# LTC2495Shield.net
KiCad netlist of a schematic drawn in EAGLE
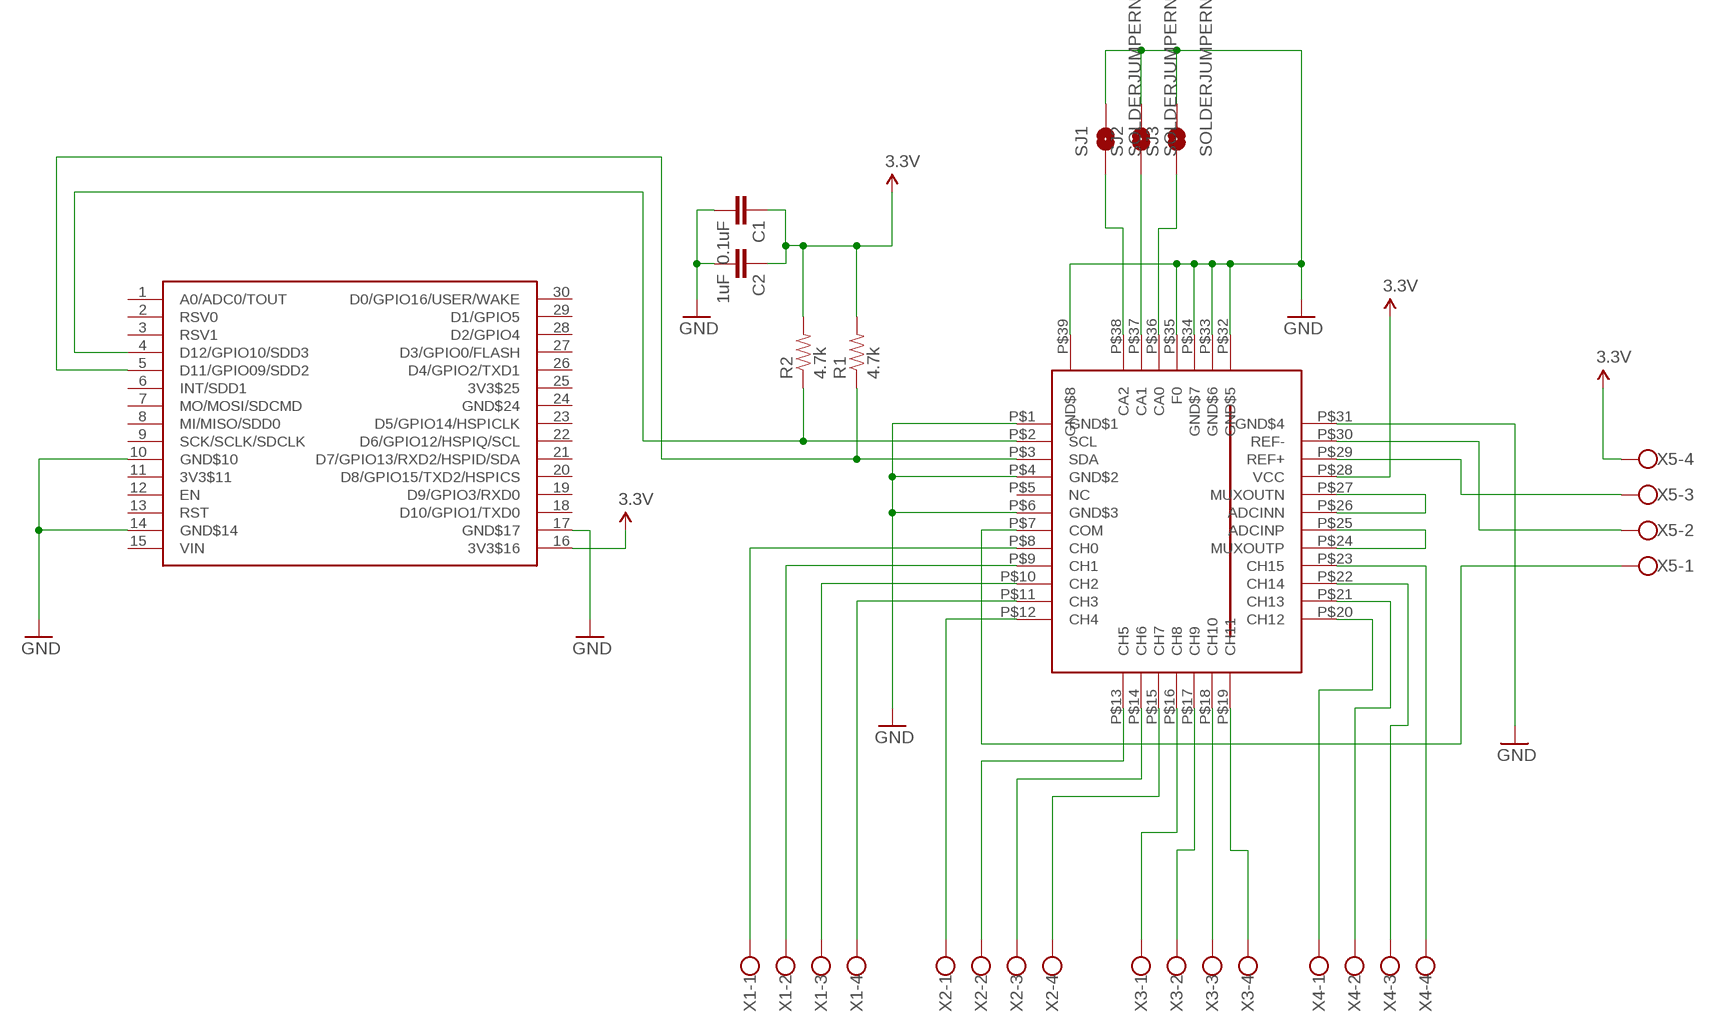
[diagram p0: schematic, sheet 1]

(export (version "E")
  (design (tool "Eeschema 10.0.6"))
  (components
    (comp (ref "C1")
      (value "0.1uF")
      (footprint "eagle-import:0402-CAP")
      (libsource (lib "eagle-import") (part "CAP0402-CAP"))
    )
    (comp (ref "C2")
      (value "1uF")
      (footprint "eagle-import:0402-CAP")
      (libsource (lib "eagle-import") (part "CAP0402-CAP"))
    )
    (comp (ref "R1")
      (value "4.7k")
      (footprint "eagle-import:0402-RES")
      (libsource (lib "eagle-import") (part "RESISTOR0402-RES"))
    )
    (comp (ref "R2")
      (value "4.7k")
      (footprint "eagle-import:0402-RES")
      (libsource (lib "eagle-import") (part "RESISTOR0402-RES"))
    )
    (comp (ref "SJ1")
      (value "SOLDERJUMPERNO")
      (footprint "eagle-import:SJ_2S-NO")
      (libsource (lib "eagle-import") (part "SOLDERJUMPERNO"))
    )
    (comp (ref "SJ2")
      (value "SOLDERJUMPERNO")
      (footprint "eagle-import:SJ_2S-NO")
      (libsource (lib "eagle-import") (part "SOLDERJUMPERNO"))
    )
    (comp (ref "SJ3")
      (value "SOLDERJUMPERNO")
      (footprint "eagle-import:SJ_2S-NO")
      (libsource (lib "eagle-import") (part "SOLDERJUMPERNO"))
    )
    (comp (ref "U$1")
      (value "NERDSHIELD")
      (footprint "eagle-import:NERDUINO_STACK")
      (libsource (lib "eagle-import") (part "NERDSHIELD"))
    )
    (comp (ref "U$3")
      (value "LTC2495")
      (footprint "eagle-import:UHF38")
      (libsource (lib "eagle-import") (part "LTC2495"))
    )
    (comp (ref "X1")
      (value "W237-4")
      (footprint "eagle-import:W237-4")
      (libsource (lib "eagle-import") (part "W237-4"))
    )
    (comp (ref "X2")
      (value "W237-4")
      (footprint "eagle-import:W237-4")
      (libsource (lib "eagle-import") (part "W237-4"))
    )
    (comp (ref "X3")
      (value "W237-4")
      (footprint "eagle-import:W237-4")
      (libsource (lib "eagle-import") (part "W237-4"))
    )
    (comp (ref "X4")
      (value "W237-4")
      (footprint "eagle-import:W237-4")
      (libsource (lib "eagle-import") (part "W237-4"))
    )
    (comp (ref "X5")
      (value "W237-4")
      (footprint "eagle-import:W237-4")
      (libsource (lib "eagle-import") (part "W237-4"))
    )
  )
  (nets
    (net (code "1") (name "3.3V") (class "Default")
      (node (ref "C1") (pin "1") (pinfunction "1_1") (pintype "passive"))
      (node (ref "C2") (pin "1") (pinfunction "1_1") (pintype "passive"))
      (node (ref "R1") (pin "2") (pinfunction "2_2") (pintype "passive"))
      (node (ref "R2") (pin "2") (pinfunction "2_2") (pintype "passive"))
      (node (ref "U$1") (pin "16") (pinfunction "3V3$16_16") (pintype "bidirectional"))
      (node (ref "U$3") (pin "P$28") (pinfunction "VCC_P$28") (pintype "bidirectional"))
      (node (ref "X5") (pin "4") (pinfunction "KL_4") (pintype "passive"))
    )
    (net (code "2") (name "GND") (class "Default")
      (node (ref "C1") (pin "2") (pinfunction "2_2") (pintype "passive"))
      (node (ref "C2") (pin "2") (pinfunction "2_2") (pintype "passive"))
      (node (ref "SJ1") (pin "2") (pinfunction "2_2") (pintype "passive"))
      (node (ref "SJ2") (pin "2") (pinfunction "2_2") (pintype "passive"))
      (node (ref "SJ3") (pin "2") (pinfunction "2_2") (pintype "passive"))
      (node (ref "U$1") (pin "10") (pinfunction "GND$10_10") (pintype "bidirectional"))
      (node (ref "U$1") (pin "14") (pinfunction "GND$14_14") (pintype "bidirectional"))
      (node (ref "U$1") (pin "17") (pinfunction "GND$17_17") (pintype "bidirectional"))
      (node (ref "U$3") (pin "P$1") (pinfunction "GND$1_P$1") (pintype "bidirectional"))
      (node (ref "U$3") (pin "P$31") (pinfunction "GND$4_P$31") (pintype "bidirectional"))
      (node (ref "U$3") (pin "P$32") (pinfunction "GND$5_P$32") (pintype "bidirectional"))
      (node (ref "U$3") (pin "P$33") (pinfunction "GND$6_P$33") (pintype "bidirectional"))
      (node (ref "U$3") (pin "P$34") (pinfunction "GND$7_P$34") (pintype "bidirectional"))
      (node (ref "U$3") (pin "P$35") (pinfunction "F0_P$35") (pintype "bidirectional"))
      (node (ref "U$3") (pin "P$39") (pinfunction "GND$8_P$39") (pintype "bidirectional"))
      (node (ref "U$3") (pin "P$4") (pinfunction "GND$2_P$4") (pintype "bidirectional"))
      (node (ref "U$3") (pin "P$6") (pinfunction "GND$3_P$6") (pintype "bidirectional"))
    )
    (net (code "3") (name "Net-(U$1-D11{slash}GPIO09{slash}SDD2)") (class "Default")
      (node (ref "R1") (pin "1") (pinfunction "1_1") (pintype "passive"))
      (node (ref "U$1") (pin "5") (pinfunction "D11/GPIO09/SDD2_5") (pintype "bidirectional"))
      (node (ref "U$3") (pin "P$3") (pinfunction "SDA_P$3") (pintype "bidirectional"))
    )
    (net (code "4") (name "Net-(U$1-D12{slash}GPIO10{slash}SDD3)") (class "Default")
      (node (ref "R2") (pin "1") (pinfunction "1_1") (pintype "passive"))
      (node (ref "U$1") (pin "4") (pinfunction "D12/GPIO10/SDD3_4") (pintype "bidirectional"))
      (node (ref "U$3") (pin "P$2") (pinfunction "SCL_P$2") (pintype "bidirectional"))
    )
    (net (code "5") (name "Net-(U$3-ADCINN)") (class "Default")
      (node (ref "U$3") (pin "P$26") (pinfunction "ADCINN_P$26") (pintype "bidirectional"))
      (node (ref "U$3") (pin "P$27") (pinfunction "MUXOUTN_P$27") (pintype "bidirectional"))
    )
    (net (code "6") (name "Net-(U$3-ADCINP)") (class "Default")
      (node (ref "U$3") (pin "P$24") (pinfunction "MUXOUTP_P$24") (pintype "bidirectional"))
      (node (ref "U$3") (pin "P$25") (pinfunction "ADCINP_P$25") (pintype "bidirectional"))
    )
    (net (code "7") (name "Net-(U$3-CA0)") (class "Default")
      (node (ref "SJ3") (pin "1") (pinfunction "1_1") (pintype "passive"))
      (node (ref "U$3") (pin "P$36") (pinfunction "CA0_P$36") (pintype "bidirectional"))
    )
    (net (code "8") (name "Net-(U$3-CA1)") (class "Default")
      (node (ref "SJ2") (pin "1") (pinfunction "1_1") (pintype "passive"))
      (node (ref "U$3") (pin "P$37") (pinfunction "CA1_P$37") (pintype "bidirectional"))
    )
    (net (code "9") (name "Net-(U$3-CA2)") (class "Default")
      (node (ref "SJ1") (pin "1") (pinfunction "1_1") (pintype "passive"))
      (node (ref "U$3") (pin "P$38") (pinfunction "CA2_P$38") (pintype "bidirectional"))
    )
    (net (code "10") (name "Net-(U$3-CH0)") (class "Default")
      (node (ref "U$3") (pin "P$8") (pinfunction "CH0_P$8") (pintype "bidirectional"))
      (node (ref "X1") (pin "1") (pinfunction "KL_1") (pintype "passive"))
    )
    (net (code "11") (name "Net-(U$3-CH1)") (class "Default")
      (node (ref "U$3") (pin "P$9") (pinfunction "CH1_P$9") (pintype "bidirectional"))
      (node (ref "X1") (pin "2") (pinfunction "KL_2") (pintype "passive"))
    )
    (net (code "12") (name "Net-(U$3-CH2)") (class "Default")
      (node (ref "U$3") (pin "P$10") (pinfunction "CH2_P$10") (pintype "bidirectional"))
      (node (ref "X1") (pin "3") (pinfunction "KL_3") (pintype "passive"))
    )
    (net (code "13") (name "Net-(U$3-CH3)") (class "Default")
      (node (ref "U$3") (pin "P$11") (pinfunction "CH3_P$11") (pintype "bidirectional"))
      (node (ref "X1") (pin "4") (pinfunction "KL_4") (pintype "passive"))
    )
    (net (code "14") (name "Net-(U$3-CH4)") (class "Default")
      (node (ref "U$3") (pin "P$12") (pinfunction "CH4_P$12") (pintype "bidirectional"))
      (node (ref "X2") (pin "1") (pinfunction "KL_1") (pintype "passive"))
    )
    (net (code "15") (name "Net-(U$3-CH5)") (class "Default")
      (node (ref "U$3") (pin "P$13") (pinfunction "CH5_P$13") (pintype "bidirectional"))
      (node (ref "X2") (pin "2") (pinfunction "KL_2") (pintype "passive"))
    )
    (net (code "16") (name "Net-(U$3-CH6)") (class "Default")
      (node (ref "U$3") (pin "P$14") (pinfunction "CH6_P$14") (pintype "bidirectional"))
      (node (ref "X2") (pin "3") (pinfunction "KL_3") (pintype "passive"))
    )
    (net (code "17") (name "Net-(U$3-CH7)") (class "Default")
      (node (ref "U$3") (pin "P$15") (pinfunction "CH7_P$15") (pintype "bidirectional"))
      (node (ref "X2") (pin "4") (pinfunction "KL_4") (pintype "passive"))
    )
    (net (code "18") (name "Net-(U$3-CH8)") (class "Default")
      (node (ref "U$3") (pin "P$16") (pinfunction "CH8_P$16") (pintype "bidirectional"))
      (node (ref "X3") (pin "1") (pinfunction "KL_1") (pintype "passive"))
    )
    (net (code "19") (name "Net-(U$3-CH9)") (class "Default")
      (node (ref "U$3") (pin "P$17") (pinfunction "CH9_P$17") (pintype "bidirectional"))
      (node (ref "X3") (pin "2") (pinfunction "KL_2") (pintype "passive"))
    )
    (net (code "20") (name "Net-(U$3-CH10)") (class "Default")
      (node (ref "U$3") (pin "P$18") (pinfunction "CH10_P$18") (pintype "bidirectional"))
      (node (ref "X3") (pin "3") (pinfunction "KL_3") (pintype "passive"))
    )
    (net (code "21") (name "Net-(U$3-CH11)") (class "Default")
      (node (ref "U$3") (pin "P$19") (pinfunction "CH11_P$19") (pintype "bidirectional"))
      (node (ref "X3") (pin "4") (pinfunction "KL_4") (pintype "passive"))
    )
    (net (code "22") (name "Net-(U$3-CH12)") (class "Default")
      (node (ref "U$3") (pin "P$20") (pinfunction "CH12_P$20") (pintype "bidirectional"))
      (node (ref "X4") (pin "1") (pinfunction "KL_1") (pintype "passive"))
    )
    (net (code "23") (name "Net-(U$3-CH13)") (class "Default")
      (node (ref "U$3") (pin "P$21") (pinfunction "CH13_P$21") (pintype "bidirectional"))
      (node (ref "X4") (pin "2") (pinfunction "KL_2") (pintype "passive"))
    )
    (net (code "24") (name "Net-(U$3-CH14)") (class "Default")
      (node (ref "U$3") (pin "P$22") (pinfunction "CH14_P$22") (pintype "bidirectional"))
      (node (ref "X4") (pin "3") (pinfunction "KL_3") (pintype "passive"))
    )
    (net (code "25") (name "Net-(U$3-CH15)") (class "Default")
      (node (ref "U$3") (pin "P$23") (pinfunction "CH15_P$23") (pintype "bidirectional"))
      (node (ref "X4") (pin "4") (pinfunction "KL_4") (pintype "passive"))
    )
    (net (code "26") (name "Net-(U$3-COM)") (class "Default")
      (node (ref "U$3") (pin "P$7") (pinfunction "COM_P$7") (pintype "bidirectional"))
      (node (ref "X5") (pin "1") (pinfunction "KL_1") (pintype "passive"))
    )
    (net (code "27") (name "Net-(U$3-REF+)") (class "Default")
      (node (ref "U$3") (pin "P$29") (pinfunction "REF+_P$29") (pintype "bidirectional"))
      (node (ref "X5") (pin "3") (pinfunction "KL_3") (pintype "passive"))
    )
    (net (code "28") (name "Net-(U$3-REF-)") (class "Default")
      (node (ref "U$3") (pin "P$30") (pinfunction "REF-_P$30") (pintype "bidirectional"))
      (node (ref "X5") (pin "2") (pinfunction "KL_2") (pintype "passive"))
    )
    (net (code "29") (name "unconnected-(U$1-3V3$11-Pad11)") (class "Default")
      (node (ref "U$1") (pin "11") (pinfunction "3V3$11_11") (pintype "bidirectional"))
    )
    (net (code "30") (name "unconnected-(U$1-3V3$25-Pad25)") (class "Default")
      (node (ref "U$1") (pin "25") (pinfunction "3V3$25_25") (pintype "bidirectional"))
    )
    (net (code "31") (name "unconnected-(U$1-A0{slash}ADC0{slash}TOUT-Pad1)") (class "Default")
      (node (ref "U$1") (pin "1") (pinfunction "A0/ADC0/TOUT_1") (pintype "bidirectional"))
    )
    (net (code "32") (name "unconnected-(U$1-D0{slash}GPIO16{slash}USER{slash}WAKE-Pad30)") (class "Default")
      (node (ref "U$1") (pin "30") (pinfunction "D0/GPIO16/USER/WAKE_30") (pintype "bidirectional"))
    )
    (net (code "33") (name "unconnected-(U$1-D1{slash}GPIO5-Pad29)") (class "Default")
      (node (ref "U$1") (pin "29") (pinfunction "D1/GPIO5_29") (pintype "bidirectional"))
    )
    (net (code "34") (name "unconnected-(U$1-D2{slash}GPIO4-Pad28)") (class "Default")
      (node (ref "U$1") (pin "28") (pinfunction "D2/GPIO4_28") (pintype "bidirectional"))
    )
    (net (code "35") (name "unconnected-(U$1-D3{slash}GPIO0{slash}FLASH-Pad27)") (class "Default")
      (node (ref "U$1") (pin "27") (pinfunction "D3/GPIO0/FLASH_27") (pintype "bidirectional"))
    )
    (net (code "36") (name "unconnected-(U$1-D4{slash}GPIO2{slash}TXD1-Pad26)") (class "Default")
      (node (ref "U$1") (pin "26") (pinfunction "D4/GPIO2/TXD1_26") (pintype "bidirectional"))
    )
    (net (code "37") (name "unconnected-(U$1-D5{slash}GPIO14{slash}HSPICLK-Pad23)") (class "Default")
      (node (ref "U$1") (pin "23") (pinfunction "D5/GPIO14/HSPICLK_23") (pintype "bidirectional"))
    )
    (net (code "38") (name "unconnected-(U$1-D6{slash}GPIO12{slash}HSPIQ{slash}SCL-Pad22)") (class "Default")
      (node (ref "U$1") (pin "22") (pinfunction "D6/GPIO12/HSPIQ/SCL_22") (pintype "bidirectional"))
    )
    (net (code "39") (name "unconnected-(U$1-D7{slash}GPIO13{slash}RXD2{slash}HSPID{slash}SDA-Pad21)") (class "Default")
      (node (ref "U$1") (pin "21") (pinfunction "D7/GPIO13/RXD2/HSPID/SDA_21") (pintype "bidirectional"))
    )
    (net (code "40") (name "unconnected-(U$1-D8{slash}GPIO15{slash}TXD2{slash}HSPICS-Pad20)") (class "Default")
      (node (ref "U$1") (pin "20") (pinfunction "D8/GPIO15/TXD2/HSPICS_20") (pintype "bidirectional"))
    )
    (net (code "41") (name "unconnected-(U$1-D9{slash}GPIO3{slash}RXD0-Pad19)") (class "Default")
      (node (ref "U$1") (pin "19") (pinfunction "D9/GPIO3/RXD0_19") (pintype "bidirectional"))
    )
    (net (code "42") (name "unconnected-(U$1-D10{slash}GPIO1{slash}TXD0-Pad18)") (class "Default")
      (node (ref "U$1") (pin "18") (pinfunction "D10/GPIO1/TXD0_18") (pintype "bidirectional"))
    )
    (net (code "43") (name "unconnected-(U$1-EN-Pad12)") (class "Default")
      (node (ref "U$1") (pin "12") (pinfunction "EN_12") (pintype "bidirectional"))
    )
    (net (code "44") (name "unconnected-(U$1-GND$24-Pad24)") (class "Default")
      (node (ref "U$1") (pin "24") (pinfunction "GND$24_24") (pintype "bidirectional"))
    )
    (net (code "45") (name "unconnected-(U$1-INT{slash}SDD1-Pad6)") (class "Default")
      (node (ref "U$1") (pin "6") (pinfunction "INT/SDD1_6") (pintype "bidirectional"))
    )
    (net (code "46") (name "unconnected-(U$1-MI{slash}MISO{slash}SDD0-Pad8)") (class "Default")
      (node (ref "U$1") (pin "8") (pinfunction "MI/MISO/SDD0_8") (pintype "bidirectional"))
    )
    (net (code "47") (name "unconnected-(U$1-MO{slash}MOSI{slash}SDCMD-Pad7)") (class "Default")
      (node (ref "U$1") (pin "7") (pinfunction "MO/MOSI/SDCMD_7") (pintype "bidirectional"))
    )
    (net (code "48") (name "unconnected-(U$1-RST-Pad13)") (class "Default")
      (node (ref "U$1") (pin "13") (pinfunction "RST_13") (pintype "bidirectional"))
    )
    (net (code "49") (name "unconnected-(U$1-RSV0-Pad2)") (class "Default")
      (node (ref "U$1") (pin "2") (pinfunction "RSV0_2") (pintype "bidirectional"))
    )
    (net (code "50") (name "unconnected-(U$1-RSV1-Pad3)") (class "Default")
      (node (ref "U$1") (pin "3") (pinfunction "RSV1_3") (pintype "bidirectional"))
    )
    (net (code "51") (name "unconnected-(U$1-SCK{slash}SCLK{slash}SDCLK-Pad9)") (class "Default")
      (node (ref "U$1") (pin "9") (pinfunction "SCK/SCLK/SDCLK_9") (pintype "bidirectional"))
    )
    (net (code "52") (name "unconnected-(U$1-VIN-Pad15)") (class "Default")
      (node (ref "U$1") (pin "15") (pinfunction "VIN_15") (pintype "bidirectional"))
    )
    (net (code "53") (name "unconnected-(U$3-NC-PadP$5)") (class "Default")
      (node (ref "U$3") (pin "P$5") (pinfunction "NC_P$5") (pintype "bidirectional"))
    )
  )
)
